# YOTSUBA_AP-ex_EM_ver_3_0.net
KiCad netlist of a schematic drawn in EAGLE
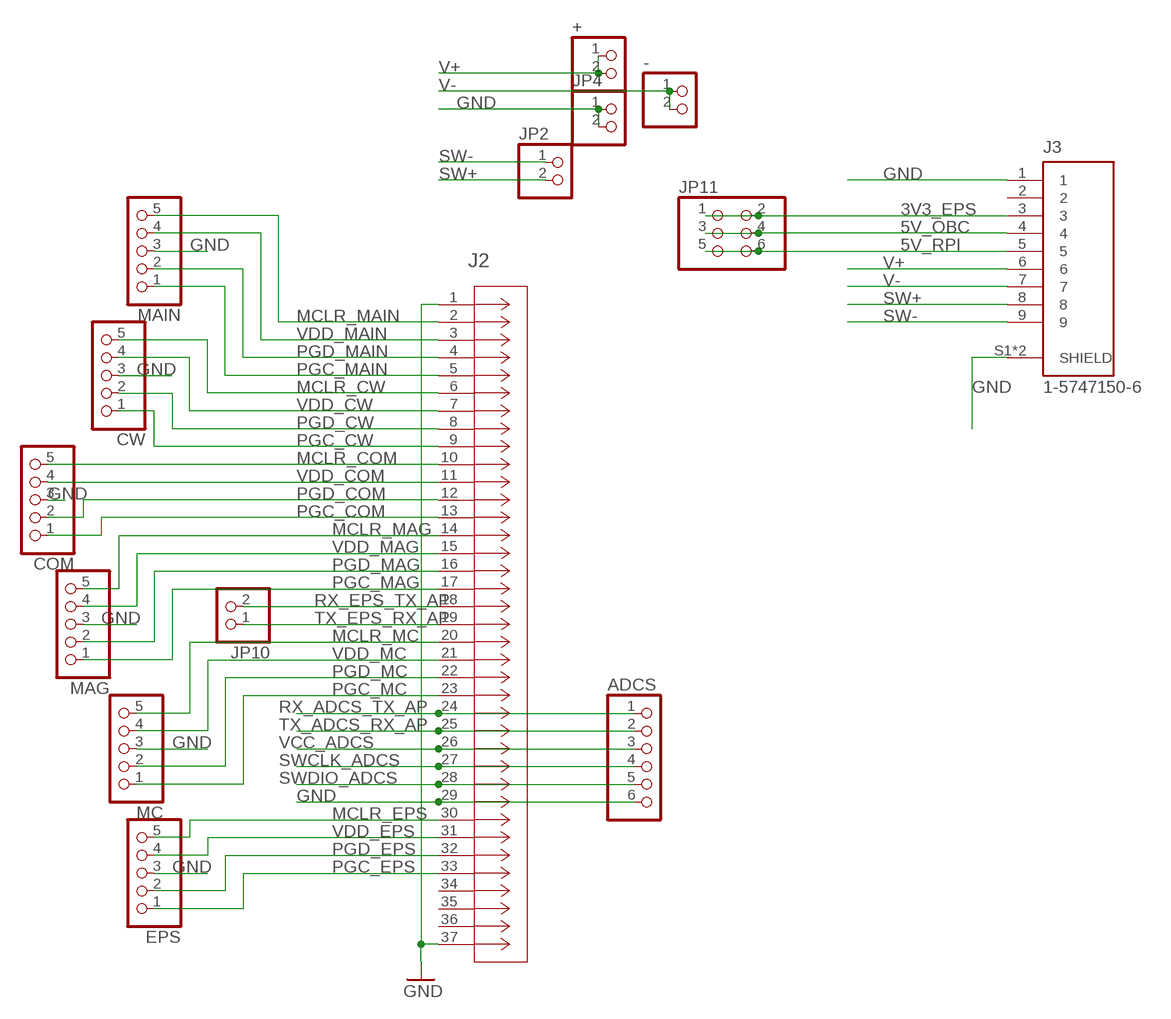
[diagram p0: schematic, sheet 1]

(export (version "E")
  (design (tool "Eeschema 10.0.6"))
  (components
    (comp (ref "+")
      (value "PINHD-1X2")
      (footprint "eagle-import:1X02")
      (libsource (lib "eagle-import") (part "PINHD-1X2"))
    )
    (comp (ref "-")
      (value "PINHD-1X2")
      (footprint "eagle-import:1X02")
      (libsource (lib "eagle-import") (part "PINHD-1X2"))
    )
    (comp (ref "ADCS")
      (value "PINHD-1X6")
      (footprint "eagle-import:1X06")
      (libsource (lib "eagle-import") (part "PINHD-1X6"))
    )
    (comp (ref "COM")
      (value "PINHD-1X5")
      (footprint "eagle-import:1X05")
      (libsource (lib "eagle-import") (part "PINHD-1X5"))
    )
    (comp (ref "CW")
      (value "PINHD-1X5")
      (footprint "eagle-import:1X05")
      (libsource (lib "eagle-import") (part "PINHD-1X5"))
    )
    (comp (ref "EPS")
      (value "PINHD-1X5")
      (footprint "eagle-import:1X05")
      (libsource (lib "eagle-import") (part "PINHD-1X5"))
    )
    (comp (ref "J2")
      (value "1-5747301-6")
      (footprint "eagle-import:CONN_1-5747301-6_TYC")
      (fields (field (name "COPYRIGHT") "Copyright (C) 2023 Ultra Librarian. All rights reserved."))
      (libsource (lib "eagle-import") (part "1-5747301-6"))
    )
    (comp (ref "J3")
      (value "1-5747150-6")
      (footprint "eagle-import:TE_1-5747150-6")
      (fields (field (name "MF") "TE Connectivity"))
      (libsource (lib "eagle-import") (part "1-5747150-6"))
    )
    (comp (ref "JP2")
      (value "PINHD-1X2")
      (footprint "eagle-import:1X02")
      (libsource (lib "eagle-import") (part "PINHD-1X2"))
    )
    (comp (ref "JP4")
      (value "PINHD-1X2")
      (footprint "eagle-import:1X02")
      (libsource (lib "eagle-import") (part "PINHD-1X2"))
    )
    (comp (ref "JP10")
      (value "PINHD-1X2")
      (footprint "eagle-import:1X02")
      (libsource (lib "eagle-import") (part "PINHD-1X2"))
    )
    (comp (ref "JP11")
      (value "PINHD-2X3")
      (footprint "eagle-import:2X03")
      (libsource (lib "eagle-import") (part "PINHD-2X3"))
    )
    (comp (ref "MAG")
      (value "PINHD-1X5")
      (footprint "eagle-import:1X05")
      (libsource (lib "eagle-import") (part "PINHD-1X5"))
    )
    (comp (ref "MAIN")
      (value "PINHD-1X5")
      (footprint "eagle-import:1X05")
      (libsource (lib "eagle-import") (part "PINHD-1X5"))
    )
    (comp (ref "MC")
      (value "PINHD-1X5")
      (footprint "eagle-import:1X05")
      (libsource (lib "eagle-import") (part "PINHD-1X5"))
    )
  )
  (nets
    (net (code "1") (name "/3V3_EPS") (class "Default")
      (node (ref "J3") (pin "3") (pinfunction "3_3") (pintype "passive"))
      (node (ref "JP11") (pin "1") (pinfunction "1_1") (pintype "passive"))
      (node (ref "JP11") (pin "2") (pinfunction "2_2") (pintype "passive"))
    )
    (net (code "2") (name "/5V_OBC") (class "Default")
      (node (ref "J3") (pin "4") (pinfunction "4_4") (pintype "passive"))
      (node (ref "JP11") (pin "3") (pinfunction "3_3") (pintype "passive"))
      (node (ref "JP11") (pin "4") (pinfunction "4_4") (pintype "passive"))
    )
    (net (code "3") (name "/5V_RPI") (class "Default")
      (node (ref "J3") (pin "5") (pinfunction "5_5") (pintype "passive"))
      (node (ref "JP11") (pin "5") (pinfunction "5_5") (pintype "passive"))
      (node (ref "JP11") (pin "6") (pinfunction "6_6") (pintype "passive"))
    )
    (net (code "4") (name "/MCLR_COM") (class "Default")
      (node (ref "COM") (pin "5") (pinfunction "5_5") (pintype "passive"))
      (node (ref "J2") (pin "10") (pinfunction "10_10") (pintype "passive"))
    )
    (net (code "5") (name "/MCLR_CW") (class "Default")
      (node (ref "CW") (pin "5") (pinfunction "5_5") (pintype "passive"))
      (node (ref "J2") (pin "6") (pinfunction "6_6") (pintype "passive"))
    )
    (net (code "6") (name "/MCLR_EPS") (class "Default")
      (node (ref "EPS") (pin "5") (pinfunction "5_5") (pintype "passive"))
      (node (ref "J2") (pin "30") (pinfunction "30_30") (pintype "passive"))
    )
    (net (code "7") (name "/MCLR_MAG") (class "Default")
      (node (ref "J2") (pin "14") (pinfunction "14_14") (pintype "passive"))
      (node (ref "MAG") (pin "5") (pinfunction "5_5") (pintype "passive"))
    )
    (net (code "8") (name "/MCLR_MAIN") (class "Default")
      (node (ref "J2") (pin "2") (pinfunction "2_2") (pintype "passive"))
      (node (ref "MAIN") (pin "5") (pinfunction "5_5") (pintype "passive"))
    )
    (net (code "9") (name "/MCLR_MC") (class "Default")
      (node (ref "J2") (pin "20") (pinfunction "20_20") (pintype "passive"))
      (node (ref "MC") (pin "5") (pinfunction "5_5") (pintype "passive"))
    )
    (net (code "10") (name "/PGC_COM") (class "Default")
      (node (ref "COM") (pin "1") (pinfunction "1_1") (pintype "passive"))
      (node (ref "J2") (pin "13") (pinfunction "13_13") (pintype "passive"))
    )
    (net (code "11") (name "/PGC_CW") (class "Default")
      (node (ref "CW") (pin "1") (pinfunction "1_1") (pintype "passive"))
      (node (ref "J2") (pin "9") (pinfunction "9_9") (pintype "passive"))
    )
    (net (code "12") (name "/PGC_EPS") (class "Default")
      (node (ref "EPS") (pin "1") (pinfunction "1_1") (pintype "passive"))
      (node (ref "J2") (pin "33") (pinfunction "33_33") (pintype "passive"))
    )
    (net (code "13") (name "/PGC_MAG") (class "Default")
      (node (ref "J2") (pin "17") (pinfunction "17_17") (pintype "passive"))
      (node (ref "MAG") (pin "1") (pinfunction "1_1") (pintype "passive"))
    )
    (net (code "14") (name "/PGC_MAIN") (class "Default")
      (node (ref "J2") (pin "5") (pinfunction "5_5") (pintype "passive"))
      (node (ref "MAIN") (pin "1") (pinfunction "1_1") (pintype "passive"))
    )
    (net (code "15") (name "/PGC_MC") (class "Default")
      (node (ref "J2") (pin "23") (pinfunction "23_23") (pintype "passive"))
      (node (ref "MC") (pin "1") (pinfunction "1_1") (pintype "passive"))
    )
    (net (code "16") (name "/PGD_COM") (class "Default")
      (node (ref "COM") (pin "2") (pinfunction "2_2") (pintype "passive"))
      (node (ref "J2") (pin "12") (pinfunction "12_12") (pintype "passive"))
    )
    (net (code "17") (name "/PGD_CW") (class "Default")
      (node (ref "CW") (pin "2") (pinfunction "2_2") (pintype "passive"))
      (node (ref "J2") (pin "8") (pinfunction "8_8") (pintype "passive"))
    )
    (net (code "18") (name "/PGD_EPS") (class "Default")
      (node (ref "EPS") (pin "2") (pinfunction "2_2") (pintype "passive"))
      (node (ref "J2") (pin "32") (pinfunction "32_32") (pintype "passive"))
    )
    (net (code "19") (name "/PGD_MAG") (class "Default")
      (node (ref "J2") (pin "16") (pinfunction "16_16") (pintype "passive"))
      (node (ref "MAG") (pin "2") (pinfunction "2_2") (pintype "passive"))
    )
    (net (code "20") (name "/PGD_MAIN") (class "Default")
      (node (ref "J2") (pin "4") (pinfunction "4_4") (pintype "passive"))
      (node (ref "MAIN") (pin "2") (pinfunction "2_2") (pintype "passive"))
    )
    (net (code "21") (name "/PGD_MC") (class "Default")
      (node (ref "J2") (pin "22") (pinfunction "22_22") (pintype "passive"))
      (node (ref "MC") (pin "2") (pinfunction "2_2") (pintype "passive"))
    )
    (net (code "22") (name "/RX_ADCS_TX_AP") (class "Default")
      (node (ref "ADCS") (pin "1") (pinfunction "1_1") (pintype "passive"))
      (node (ref "J2") (pin "24") (pinfunction "24_24") (pintype "passive"))
    )
    (net (code "23") (name "/RX_EPS_TX_AP") (class "Default")
      (node (ref "J2") (pin "18") (pinfunction "18_18") (pintype "passive"))
      (node (ref "JP10") (pin "2") (pinfunction "2_2") (pintype "passive"))
    )
    (net (code "24") (name "/SW+") (class "Default")
      (node (ref "J3") (pin "8") (pinfunction "8_8") (pintype "passive"))
      (node (ref "JP2") (pin "2") (pinfunction "2_2") (pintype "passive"))
    )
    (net (code "25") (name "/SW-") (class "Default")
      (node (ref "J3") (pin "9") (pinfunction "9_9") (pintype "passive"))
      (node (ref "JP2") (pin "1") (pinfunction "1_1") (pintype "passive"))
    )
    (net (code "26") (name "/SWCLK_ADCS") (class "Default")
      (node (ref "ADCS") (pin "4") (pinfunction "4_4") (pintype "passive"))
      (node (ref "J2") (pin "27") (pinfunction "27_27") (pintype "passive"))
    )
    (net (code "27") (name "/SWDIO_ADCS") (class "Default")
      (node (ref "ADCS") (pin "5") (pinfunction "5_5") (pintype "passive"))
      (node (ref "J2") (pin "28") (pinfunction "28_28") (pintype "passive"))
    )
    (net (code "28") (name "/TX_ADCS_RX_AP") (class "Default")
      (node (ref "ADCS") (pin "2") (pinfunction "2_2") (pintype "passive"))
      (node (ref "J2") (pin "25") (pinfunction "25_25") (pintype "passive"))
    )
    (net (code "29") (name "/TX_EPS_RX_AP") (class "Default")
      (node (ref "J2") (pin "19") (pinfunction "19_19") (pintype "passive"))
      (node (ref "JP10") (pin "1") (pinfunction "1_1") (pintype "passive"))
    )
    (net (code "30") (name "/V+") (class "Default")
      (node (ref "+") (pin "1") (pinfunction "1_1") (pintype "passive"))
      (node (ref "+") (pin "2") (pinfunction "2_2") (pintype "passive"))
      (node (ref "J3") (pin "6") (pinfunction "6_6") (pintype "passive"))
    )
    (net (code "31") (name "/V-") (class "Default")
      (node (ref "-") (pin "1") (pinfunction "1_1") (pintype "passive"))
      (node (ref "-") (pin "2") (pinfunction "2_2") (pintype "passive"))
      (node (ref "J3") (pin "7") (pinfunction "7_7") (pintype "passive"))
    )
    (net (code "32") (name "/VCC_ADCS") (class "Default")
      (node (ref "ADCS") (pin "3") (pinfunction "3_3") (pintype "passive"))
      (node (ref "J2") (pin "26") (pinfunction "26_26") (pintype "passive"))
    )
    (net (code "33") (name "/VDD_COM") (class "Default")
      (node (ref "COM") (pin "4") (pinfunction "4_4") (pintype "passive"))
      (node (ref "J2") (pin "11") (pinfunction "11_11") (pintype "passive"))
    )
    (net (code "34") (name "/VDD_CW") (class "Default")
      (node (ref "CW") (pin "4") (pinfunction "4_4") (pintype "passive"))
      (node (ref "J2") (pin "7") (pinfunction "7_7") (pintype "passive"))
    )
    (net (code "35") (name "/VDD_EPS") (class "Default")
      (node (ref "EPS") (pin "4") (pinfunction "4_4") (pintype "passive"))
      (node (ref "J2") (pin "31") (pinfunction "31_31") (pintype "passive"))
    )
    (net (code "36") (name "/VDD_MAG") (class "Default")
      (node (ref "J2") (pin "15") (pinfunction "15_15") (pintype "passive"))
      (node (ref "MAG") (pin "4") (pinfunction "4_4") (pintype "passive"))
    )
    (net (code "37") (name "/VDD_MAIN") (class "Default")
      (node (ref "J2") (pin "3") (pinfunction "3_3") (pintype "passive"))
      (node (ref "MAIN") (pin "4") (pinfunction "4_4") (pintype "passive"))
    )
    (net (code "38") (name "/VDD_MC") (class "Default")
      (node (ref "J2") (pin "21") (pinfunction "21_21") (pintype "passive"))
      (node (ref "MC") (pin "4") (pinfunction "4_4") (pintype "passive"))
    )
    (net (code "39") (name "GND") (class "Default")
      (node (ref "ADCS") (pin "6") (pinfunction "6_6") (pintype "passive"))
      (node (ref "COM") (pin "3") (pinfunction "3_3") (pintype "passive"))
      (node (ref "CW") (pin "3") (pinfunction "3_3") (pintype "passive"))
      (node (ref "EPS") (pin "3") (pinfunction "3_3") (pintype "passive"))
      (node (ref "J2") (pin "1") (pinfunction "1_1") (pintype "passive"))
      (node (ref "J2") (pin "29") (pinfunction "29_29") (pintype "passive"))
      (node (ref "J2") (pin "37") (pinfunction "37_37") (pintype "passive"))
      (node (ref "J3") (pin "1") (pinfunction "1_1") (pintype "passive"))
      (node (ref "J3") (pin "S1") (pinfunction "SHIELD_S1") (pintype "passive"))
      (node (ref "J3") (pin "S2") (pinfunction "SHIELD_S2") (pintype "passive"))
      (node (ref "JP4") (pin "1") (pinfunction "1_1") (pintype "passive"))
      (node (ref "JP4") (pin "2") (pinfunction "2_2") (pintype "passive"))
      (node (ref "MAG") (pin "3") (pinfunction "3_3") (pintype "passive"))
      (node (ref "MAIN") (pin "3") (pinfunction "3_3") (pintype "passive"))
      (node (ref "MC") (pin "3") (pinfunction "3_3") (pintype "passive"))
    )
    (net (code "40") (name "unconnected-(J2-Pad34)") (class "Default")
      (node (ref "J2") (pin "34") (pinfunction "34_34") (pintype "passive"))
    )
    (net (code "41") (name "unconnected-(J2-Pad35)") (class "Default")
      (node (ref "J2") (pin "35") (pinfunction "35_35") (pintype "passive"))
    )
    (net (code "42") (name "unconnected-(J2-Pad36)") (class "Default")
      (node (ref "J2") (pin "36") (pinfunction "36_36") (pintype "passive"))
    )
    (net (code "43") (name "unconnected-(J3-Pad2)") (class "Default")
      (node (ref "J3") (pin "2") (pinfunction "2_2") (pintype "passive"))
    )
  )
)
